# amplificador.net
KiCad netlist of a schematic drawn in EAGLE
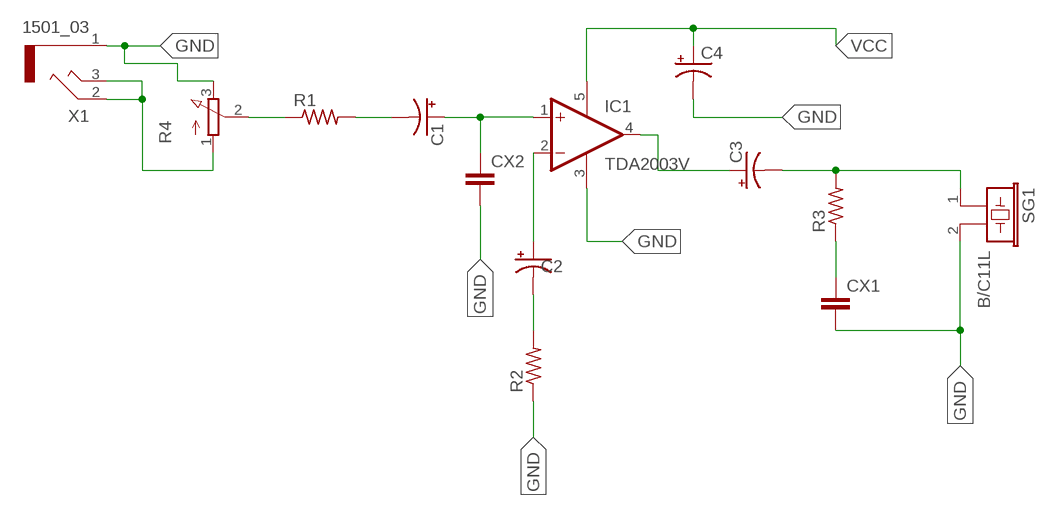
[diagram p0: schematic, sheet 1]

(export (version "E")
  (design (tool "Eeschema 10.0.6"))
  (components
    (comp (ref "C1")
      (value "CPOL-USB45181B")
      (footprint "eagle-import:B45181B")
      (libsource (lib "eagle-import") (part "CPOL-USB45181B"))
    )
    (comp (ref "C2")
      (value "CPOL-USB45181B")
      (footprint "eagle-import:B45181B")
      (libsource (lib "eagle-import") (part "CPOL-USB45181B"))
    )
    (comp (ref "C3")
      (value "CPOL-USB45181B")
      (footprint "eagle-import:B45181B")
      (libsource (lib "eagle-import") (part "CPOL-USB45181B"))
    )
    (comp (ref "C4")
      (value "CPOL-USB45181B")
      (footprint "eagle-import:B45181B")
      (libsource (lib "eagle-import") (part "CPOL-USB45181B"))
    )
    (comp (ref "CX1")
      (value "CXXC10B6")
      (footprint "eagle-import:XC10B6")
      (libsource (lib "eagle-import") (part "CXXC10B6"))
    )
    (comp (ref "CX2")
      (value "CXXC10B6")
      (footprint "eagle-import:XC10B6")
      (libsource (lib "eagle-import") (part "CXXC10B6"))
    )
    (comp (ref "IC1")
      (value "TDA2003V")
      (footprint "eagle-import:CB360")
      (libsource (lib "eagle-import") (part "TDA2003V"))
    )
    (comp (ref "R1")
      (value "R-US_0204/7")
      (footprint "eagle-import:0204_7")
      (libsource (lib "eagle-import") (part "R-US_0204/7"))
    )
    (comp (ref "R2")
      (value "R-US_0204/7")
      (footprint "eagle-import:0204_7")
      (libsource (lib "eagle-import") (part "R-US_0204/7"))
    )
    (comp (ref "R3")
      (value "R-US_0204/7")
      (footprint "eagle-import:0204_7")
      (libsource (lib "eagle-import") (part "R-US_0204/7"))
    )
    (comp (ref "R4")
      (value "3RP/1610N")
      (footprint "eagle-import:3RP_1610N")
      (libsource (lib "eagle-import") (part "3RP/1610N"))
    )
    (comp (ref "SG1")
      (value "B/C11L")
      (footprint "eagle-import:B_C11L")
      (libsource (lib "eagle-import") (part "B/C11L"))
    )
    (comp (ref "X1")
      (value "1501_03")
      (footprint "eagle-import:1501_03")
      (libsource (lib "eagle-import") (part "1501_03"))
    )
  )
  (nets
    (net (code "1") (name "GND") (class "Default")
      (node (ref "C4") (pin "-") (pinfunction "-_-") (pintype "passive"))
      (node (ref "CX1") (pin "2") (pinfunction "2_2") (pintype "passive"))
      (node (ref "CX2") (pin "2") (pinfunction "2_2") (pintype "passive"))
      (node (ref "IC1") (pin "3") (pinfunction "GND_3") (pintype "power_in"))
      (node (ref "R2") (pin "1") (pinfunction "1_1") (pintype "passive"))
      (node (ref "R4") (pin "3") (pinfunction "E_3") (pintype "passive"))
      (node (ref "SG1") (pin "2") (pinfunction "2_2") (pintype "passive"))
      (node (ref "X1") (pin "1") (pinfunction "1_1") (pintype "passive"))
    )
    (net (code "2") (name "Net-(C1-Pad-)") (class "Default")
      (node (ref "C1") (pin "-") (pinfunction "-_-") (pintype "passive"))
      (node (ref "R1") (pin "2") (pinfunction "2_2") (pintype "passive"))
    )
    (net (code "3") (name "Net-(C2-Pad-)") (class "Default")
      (node (ref "C2") (pin "-") (pinfunction "-_-") (pintype "passive"))
      (node (ref "R2") (pin "2") (pinfunction "2_2") (pintype "passive"))
    )
    (net (code "4") (name "Net-(C3-Pad-)") (class "Default")
      (node (ref "C3") (pin "-") (pinfunction "-_-") (pintype "passive"))
      (node (ref "R3") (pin "2") (pinfunction "2_2") (pintype "passive"))
      (node (ref "SG1") (pin "1") (pinfunction "1_1") (pintype "passive"))
    )
    (net (code "5") (name "Net-(CX1-Pad1)") (class "Default")
      (node (ref "CX1") (pin "1") (pinfunction "1_1") (pintype "passive"))
      (node (ref "R3") (pin "1") (pinfunction "1_1") (pintype "passive"))
    )
    (net (code "6") (name "Net-(IC1-+IN)") (class "Default")
      (node (ref "C1") (pin "+") (pinfunction "+_+") (pintype "passive"))
      (node (ref "CX2") (pin "1") (pinfunction "1_1") (pintype "passive"))
      (node (ref "IC1") (pin "1") (pinfunction "+IN_1") (pintype "input"))
    )
    (net (code "7") (name "Net-(IC1--IN)") (class "Default")
      (node (ref "C2") (pin "+") (pinfunction "+_+") (pintype "passive"))
      (node (ref "IC1") (pin "2") (pinfunction "-IN_2") (pintype "input"))
    )
    (net (code "8") (name "Net-(IC1-OUT)") (class "Default")
      (node (ref "C3") (pin "+") (pinfunction "+_+") (pintype "passive"))
      (node (ref "IC1") (pin "4") (pinfunction "OUT_4") (pintype "output"))
    )
    (net (code "9") (name "Net-(R4-A)") (class "Default")
      (node (ref "R4") (pin "1") (pinfunction "A_1") (pintype "passive"))
      (node (ref "X1") (pin "2") (pinfunction "2_2") (pintype "passive"))
      (node (ref "X1") (pin "3") (pinfunction "3_3") (pintype "passive"))
    )
    (net (code "10") (name "Net-(R4-S)") (class "Default")
      (node (ref "R1") (pin "1") (pinfunction "1_1") (pintype "passive"))
      (node (ref "R4") (pin "2") (pinfunction "S_2") (pintype "passive"))
    )
    (net (code "11") (name "VCC") (class "Default")
      (node (ref "C4") (pin "+") (pinfunction "+_+") (pintype "passive"))
      (node (ref "IC1") (pin "5") (pinfunction "V+_5") (pintype "power_in"))
    )
  )
)
